# lidar4_sch.net
KiCad netlist of a schematic drawn in Altium Designer
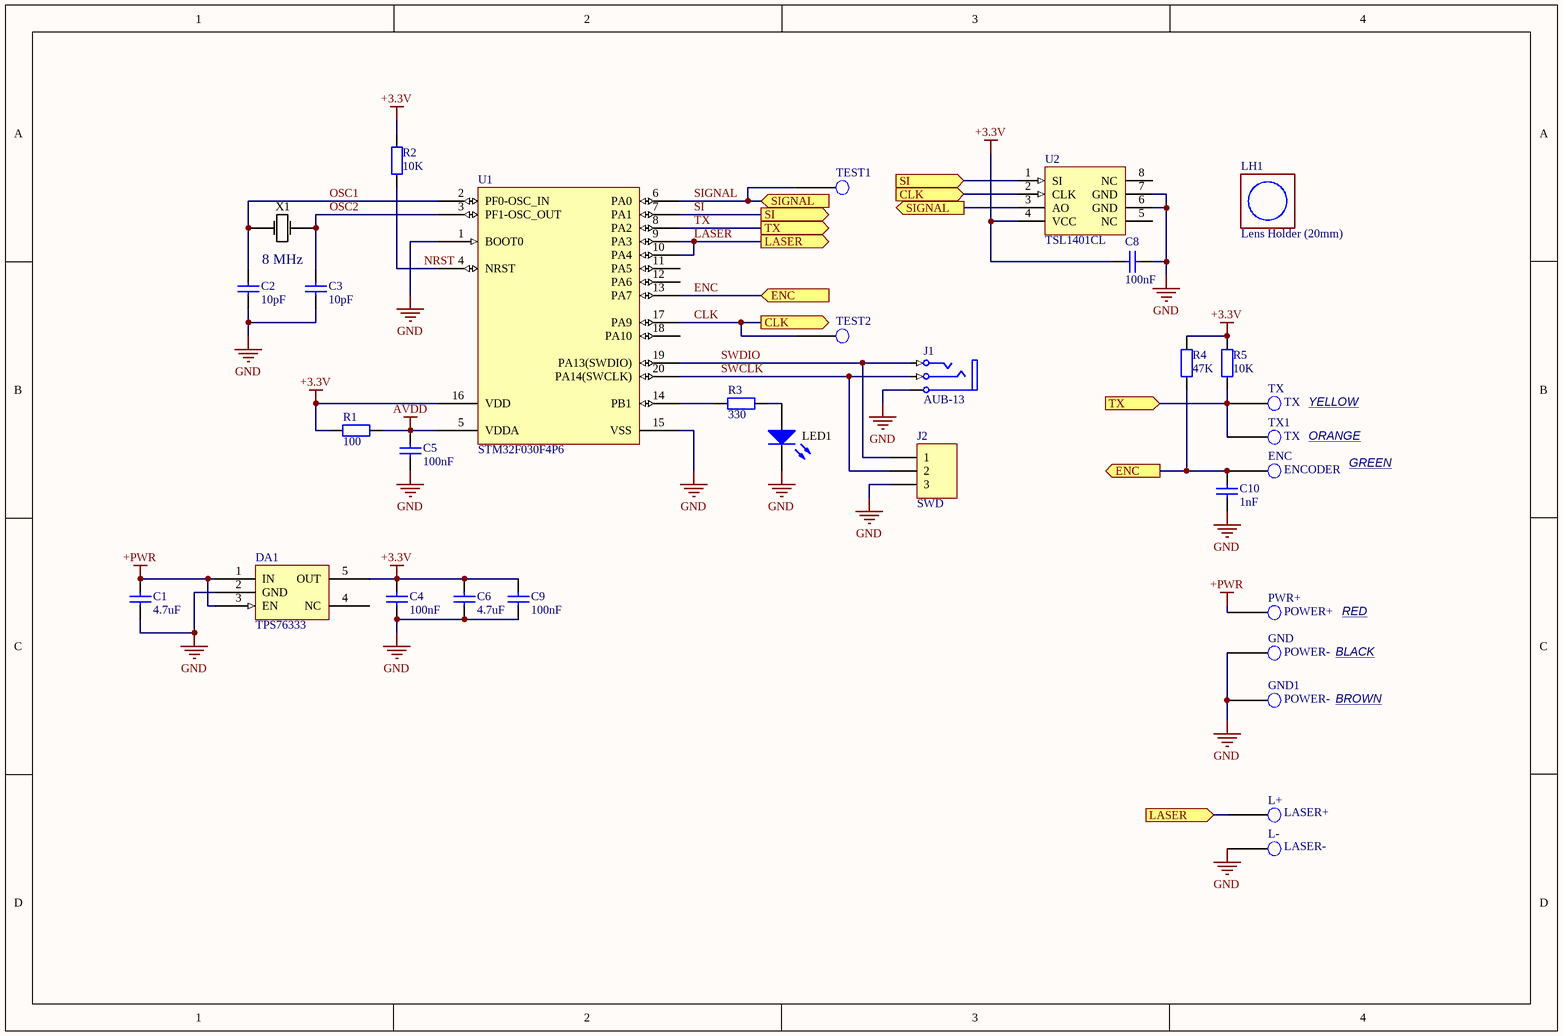
[diagram p0: lidar4_sch.SchDoc]

(export (version "E")
  (design (tool "Eeschema 10.0.6"))
  (components
    (comp (ref "C1")
      (value "4.7uF")
      (footprint "CAPC2012X135N")
      (description "Chip capacitor")
      (fields (field (name "VOLTAGE") "25V"))
      (libsource (lib "MyLibSch") (part "CC0805"))
    )
    (comp (ref "C2")
      (value "10pF")
      (footprint "CAPC1608X90N")
      (description "Chip capacitor")
      (fields (field (name "VOLTAGE") "25V"))
      (libsource (lib "MyLibSch") (part "CC0805"))
    )
    (comp (ref "C3")
      (value "10pF")
      (footprint "CAPC1608X90N")
      (description "Chip capacitor")
      (fields (field (name "VOLTAGE") "25V"))
      (libsource (lib "MyLibSch") (part "CC0805"))
    )
    (comp (ref "C4")
      (value "100nF")
      (footprint "CAPC1608X90N")
      (description "Chip capacitor")
      (fields (field (name "VOLTAGE") "25V"))
      (libsource (lib "MyLibSch") (part "CC0805"))
    )
    (comp (ref "C5")
      (value "100nF")
      (footprint "CAPC1608X90N")
      (description "Chip capacitor")
      (fields (field (name "VOLTAGE") "25V"))
      (libsource (lib "MyLibSch") (part "CC0805"))
    )
    (comp (ref "C6")
      (value "4.7uF")
      (footprint "CAPC2012X135N")
      (description "Chip capacitor")
      (fields (field (name "VOLTAGE") "25V"))
      (libsource (lib "MyLibSch") (part "CC0805"))
    )
    (comp (ref "C8")
      (value "100nF")
      (footprint "CAPC1608X90N")
      (description "Chip capacitor")
      (fields (field (name "VOLTAGE") "25V"))
      (libsource (lib "MyLibSch") (part "CC0805"))
    )
    (comp (ref "C9")
      (value "100nF")
      (footprint "CAPC1608X90N")
      (description "Chip capacitor")
      (fields (field (name "VOLTAGE") "25V"))
      (libsource (lib "MyLibSch") (part "CC0805"))
    )
    (comp (ref "C10")
      (value "1nF")
      (footprint "CAPC1608X90N")
      (description "Chip capacitor")
      (fields (field (name "VOLTAGE") "25V"))
      (libsource (lib "MyLibSch") (part "CC0805"))
    )
    (comp (ref "DA1")
      (value "TPS76333")
      (footprint "SOT23-5")
      (description "LDO")
      (libsource (lib "lcd_lib") (part "TPS76333"))
    )
    (comp (ref "ENC")
      (value "ENCODER")
      (footprint "Ext_hole")
      (description "Pad for wire")
      (libsource (lib "lcd_lib") (part "Ext Pad"))
    )
    (comp (ref "GND")
      (value "POWER-")
      (footprint "Ext_hole")
      (description "Pad for wire")
      (libsource (lib "lcd_lib") (part "Ext Pad"))
    )
    (comp (ref "GND1")
      (value "POWER-")
      (footprint "Ext_hole")
      (description "Pad for wire")
      (libsource (lib "lcd_lib") (part "Ext Pad"))
    )
    (comp (ref "J1")
      (value "AUB-13")
      (footprint "AUB-13")
      (description "Jack Socket, 1/4\" [6.5mm], Thru-Hole, Vertical, 3-Conductor Open Circuit (Non-Normalling)")
      (fields (field (name "PUBLISHER") "Altium Limited"))
      (libsource (lib "Miscellaneous Connectors") (part "Phonejack3"))
    )
    (comp (ref "J2")
      (value "SWD")
      (footprint "HDR1X3")
      (description "Header, 3-Pin")
      (fields (field (name "PUBLISHER") "Altium Limited"))
      (libsource (lib "Miscellaneous Connectors") (part "Header 3"))
    )
    (comp (ref "L+")
      (value "LASER+")
      (footprint "Ext_hole")
      (description "Pad for wire")
      (libsource (lib "lcd_lib") (part "Ext Pad"))
    )
    (comp (ref "L-")
      (value "LASER-")
      (footprint "Ext_hole")
      (description "Pad for wire")
      (libsource (lib "lcd_lib") (part "Ext Pad"))
    )
    (comp (ref "LED1")
      (value "LED")
      (footprint "PcbLib3:LED_0603")
      (description "LED_0603")
      (libsource (lib "lcd_lib") (part "LED_0603"))
    )
    (comp (ref "LH1")
      (value "Lens Holder (20mm)")
      (footprint "LENS_HOLDER_20MM_ADJ")
      (description "M12 Lens Holder")
      (libsource (lib "lcd_lib") (part "M12 Lens Holder"))
    )
    (comp (ref "PWR+")
      (value "POWER+")
      (footprint "Ext_hole")
      (description "Pad for wire")
      (libsource (lib "lcd_lib") (part "Ext Pad"))
    )
    (comp (ref "R1")
      (value "100")
      (footprint "RESC1608X55N")
      (description "Chip resistor")
      (fields (field (name "TOLERANCE") "5%"))
      (libsource (lib "") (part "RC0805_1"))
    )
    (comp (ref "R2")
      (value "10K")
      (footprint "RESC1608X55N")
      (description "Chip resistor")
      (fields (field (name "TOLERANCE") "5%"))
      (libsource (lib "MyLibSch") (part "RC0805"))
    )
    (comp (ref "R3")
      (value "330")
      (footprint "RESC1608X55N")
      (description "Chip resistor")
      (fields (field (name "TOLERANCE") "5%"))
      (libsource (lib "") (part "RC0805_2"))
    )
    (comp (ref "R4")
      (value "47K")
      (footprint "RESC1608X55N")
      (description "Chip resistor")
      (fields (field (name "TOLERANCE") "5%"))
      (libsource (lib "MyLibSch") (part "RC0805"))
    )
    (comp (ref "R5")
      (value "10K")
      (footprint "RESC1608X55N")
      (description "Chip resistor")
      (fields (field (name "TOLERANCE") "5%"))
      (libsource (lib "MyLibSch") (part "RC0805"))
    )
    (comp (ref "TEST1")
      (value "Pad")
      (footprint "PcbLib3:Ext_pad")
      (description "Pad for wire")
      (libsource (lib "lcd_lib") (part "Ext Pad"))
    )
    (comp (ref "TEST2")
      (value "Pad")
      (footprint "PcbLib3:Ext_pad")
      (description "Pad for wire")
      (libsource (lib "lcd_lib") (part "Ext Pad"))
    )
    (comp (ref "TX")
      (value "TX")
      (footprint "Ext_hole")
      (description "Pad for wire")
      (libsource (lib "lcd_lib") (part "Ext Pad"))
    )
    (comp (ref "TX1")
      (value "TX")
      (footprint "Ext_hole")
      (description "Pad for wire")
      (libsource (lib "lcd_lib") (part "Ext Pad"))
    )
    (comp (ref "U1")
      (value "STM32F030F4P6")
      (footprint "TSSOP65P640X120-20N")
      (libsource (lib "STM32 MCU") (part "STM32F030F4P6"))
    )
    (comp (ref "U2")
      (value "TSL1401CL")
      (footprint "PcbLib3:TSL1401CL_2")
      (description "Light sensor")
      (libsource (lib "lcd_lib") (part "TSL1401CL"))
    )
    (comp (ref "X1")
      (value "8 MHz")
      (footprint "SX-6 QUARTZ")
      (description "Quartz_SX-6 (SMD06035C4)")
      (fields (field (name "Comment") "Quartz"))
      (libsource (lib "lcd_lib") (part "Quartz_SX-6"))
    )
  )
  (nets
    (net (code "1") (name "+3.3V") (class "Default")
      (node (ref "C4") (pin "2") (pinfunction "2_2") (pintype "passive"))
      (node (ref "C6") (pin "2") (pinfunction "2_2") (pintype "passive"))
      (node (ref "C8") (pin "2") (pinfunction "2_2") (pintype "passive"))
      (node (ref "C9") (pin "2") (pinfunction "2_2") (pintype "passive"))
      (node (ref "DA1") (pin "5") (pinfunction "OUT_5") (pintype "passive"))
      (node (ref "R1") (pin "1") (pinfunction "1_1") (pintype "passive"))
      (node (ref "R2") (pin "1") (pinfunction "1_1") (pintype "passive"))
      (node (ref "R4") (pin "1") (pinfunction "1_1") (pintype "passive"))
      (node (ref "R5") (pin "1") (pinfunction "1_1") (pintype "passive"))
      (node (ref "U1") (pin "16") (pinfunction "VDD_16") (pintype "power_in"))
      (node (ref "U2") (pin "4") (pinfunction "VCC_4") (pintype "power_in"))
    )
    (net (code "2") (name "+PWR") (class "Default")
      (node (ref "C1") (pin "2") (pinfunction "2_2") (pintype "passive"))
      (node (ref "DA1") (pin "1") (pinfunction "IN_1") (pintype "power_in"))
      (node (ref "DA1") (pin "3") (pinfunction "EN_3") (pintype "input"))
      (node (ref "PWR+") (pin "1") (pinfunction "Pad_1") (pintype "passive"))
    )
    (net (code "3") (name "/CLK") (class "Default")
      (node (ref "TEST2") (pin "1") (pinfunction "Pad_1") (pintype "passive"))
      (node (ref "U1") (pin "17") (pinfunction "PA9_17") (pintype "bidirectional"))
      (node (ref "U2") (pin "2") (pinfunction "CLK_2") (pintype "input"))
    )
    (net (code "4") (name "/ENC") (class "Default")
      (node (ref "C10") (pin "2") (pinfunction "2_2") (pintype "passive"))
      (node (ref "ENC") (pin "1") (pinfunction "Pad_1") (pintype "passive"))
      (node (ref "R4") (pin "2") (pinfunction "2_2") (pintype "passive"))
      (node (ref "U1") (pin "13") (pinfunction "PA7_13") (pintype "bidirectional"))
    )
    (net (code "5") (name "/LASER") (class "Default")
      (node (ref "L+") (pin "1") (pinfunction "Pad_1") (pintype "passive"))
      (node (ref "U1") (pin "10") (pinfunction "PA4_10") (pintype "bidirectional"))
      (node (ref "U1") (pin "9") (pinfunction "PA3_9") (pintype "bidirectional"))
    )
    (net (code "6") (name "/NRST") (class "Default")
      (node (ref "R2") (pin "2") (pinfunction "2_2") (pintype "passive"))
      (node (ref "U1") (pin "4") (pinfunction "NRST_4") (pintype "bidirectional"))
    )
    (net (code "7") (name "/OSC1") (class "Default")
      (node (ref "C2") (pin "2") (pinfunction "2_2") (pintype "passive"))
      (node (ref "U1") (pin "2") (pinfunction "PF0-OSC_IN_2") (pintype "bidirectional"))
      (node (ref "X1") (pin "1") (pinfunction "1_1") (pintype "passive"))
    )
    (net (code "8") (name "/OSC2") (class "Default")
      (node (ref "C3") (pin "2") (pinfunction "2_2") (pintype "passive"))
      (node (ref "U1") (pin "3") (pinfunction "PF1-OSC_OUT_3") (pintype "bidirectional"))
      (node (ref "X1") (pin "3") (pinfunction "3_3") (pintype "passive"))
    )
    (net (code "9") (name "/SI") (class "Default")
      (node (ref "U1") (pin "7") (pinfunction "PA1_7") (pintype "bidirectional"))
      (node (ref "U2") (pin "1") (pinfunction "SI_1") (pintype "input"))
    )
    (net (code "10") (name "/SIGNAL") (class "Default")
      (node (ref "TEST1") (pin "1") (pinfunction "Pad_1") (pintype "passive"))
      (node (ref "U1") (pin "6") (pinfunction "PA0_6") (pintype "bidirectional"))
      (node (ref "U2") (pin "3") (pinfunction "AO_3") (pintype "passive"))
    )
    (net (code "11") (name "/SWCLK") (class "Default")
      (node (ref "J1") (pin "3") (pinfunction "R_3") (pintype "input"))
      (node (ref "J2") (pin "2") (pinfunction "2_2") (pintype "passive"))
      (node (ref "U1") (pin "20") (pinfunction "PA14(SWCLK)_20") (pintype "bidirectional"))
    )
    (net (code "12") (name "/SWDIO") (class "Default")
      (node (ref "J1") (pin "1") (pinfunction "T_1") (pintype "input"))
      (node (ref "J2") (pin "1") (pinfunction "1_1") (pintype "passive"))
      (node (ref "U1") (pin "19") (pinfunction "PA13(SWDIO)_19") (pintype "bidirectional"))
    )
    (net (code "13") (name "/TX") (class "Default")
      (node (ref "R5") (pin "2") (pinfunction "2_2") (pintype "passive"))
      (node (ref "TX") (pin "1") (pinfunction "Pad_1") (pintype "passive"))
      (node (ref "TX1") (pin "1") (pinfunction "Pad_1") (pintype "passive"))
      (node (ref "U1") (pin "8") (pinfunction "PA2_8") (pintype "bidirectional"))
    )
    (net (code "14") (name "AVDD") (class "Default")
      (node (ref "C5") (pin "2") (pinfunction "2_2") (pintype "passive"))
      (node (ref "R1") (pin "2") (pinfunction "2_2") (pintype "passive"))
      (node (ref "U1") (pin "5") (pinfunction "VDDA_5") (pintype "power_in"))
    )
    (net (code "15") (name "GND") (class "Default")
      (node (ref "C1") (pin "1") (pinfunction "1_1") (pintype "passive"))
      (node (ref "C10") (pin "1") (pinfunction "1_1") (pintype "passive"))
      (node (ref "C2") (pin "1") (pinfunction "1_1") (pintype "passive"))
      (node (ref "C3") (pin "1") (pinfunction "1_1") (pintype "passive"))
      (node (ref "C4") (pin "1") (pinfunction "1_1") (pintype "passive"))
      (node (ref "C5") (pin "1") (pinfunction "1_1") (pintype "passive"))
      (node (ref "C6") (pin "1") (pinfunction "1_1") (pintype "passive"))
      (node (ref "C8") (pin "1") (pinfunction "1_1") (pintype "passive"))
      (node (ref "C9") (pin "1") (pinfunction "1_1") (pintype "passive"))
      (node (ref "DA1") (pin "2") (pinfunction "GND_2") (pintype "power_in"))
      (node (ref "GND") (pin "1") (pinfunction "Pad_1") (pintype "passive"))
      (node (ref "GND1") (pin "1") (pinfunction "Pad_1") (pintype "passive"))
      (node (ref "J1") (pin "5") (pinfunction "S_5") (pintype "power_in"))
      (node (ref "J2") (pin "3") (pinfunction "3_3") (pintype "passive"))
      (node (ref "L-") (pin "1") (pinfunction "Pad_1") (pintype "passive"))
      (node (ref "LED1") (pin "2") (pinfunction "K_2") (pintype "passive"))
      (node (ref "U1") (pin "1") (pinfunction "BOOT0_1") (pintype "input"))
      (node (ref "U1") (pin "15") (pinfunction "VSS_15") (pintype "power_in"))
      (node (ref "U2") (pin "6") (pinfunction "GND_6") (pintype "power_in"))
      (node (ref "U2") (pin "7") (pinfunction "GND_7") (pintype "power_in"))
    )
    (net (code "16") (name "Net-(LED1-A)") (class "Default")
      (node (ref "LED1") (pin "1") (pinfunction "A_1") (pintype "passive"))
      (node (ref "R3") (pin "1") (pinfunction "1_1") (pintype "passive"))
    )
    (net (code "17") (name "Net-(U1-PB1)") (class "Default")
      (node (ref "R3") (pin "2") (pinfunction "2_2") (pintype "passive"))
      (node (ref "U1") (pin "14") (pinfunction "PB1_14") (pintype "bidirectional"))
    )
    (net (code "18") (name "unconnected-(DA1-NC-Pad4)") (class "Default")
      (node (ref "DA1") (pin "4") (pinfunction "NC_4") (pintype "passive"))
    )
    (net (code "19") (name "unconnected-(U1-PA5-Pad11)") (class "Default")
      (node (ref "U1") (pin "11") (pinfunction "PA5_11") (pintype "bidirectional"))
    )
    (net (code "20") (name "unconnected-(U1-PA6-Pad12)") (class "Default")
      (node (ref "U1") (pin "12") (pinfunction "PA6_12") (pintype "bidirectional"))
    )
    (net (code "21") (name "unconnected-(U1-PA10-Pad18)") (class "Default")
      (node (ref "U1") (pin "18") (pinfunction "PA10_18") (pintype "bidirectional"))
    )
    (net (code "22") (name "unconnected-(U2-NC-Pad5)") (class "Default")
      (node (ref "U2") (pin "5") (pinfunction "NC_5") (pintype "passive"))
    )
    (net (code "23") (name "unconnected-(U2-NC-Pad8)") (class "Default")
      (node (ref "U2") (pin "8") (pinfunction "NC_8") (pintype "passive"))
    )
  )
)
